# DAC_channel.net
KiCad netlist of a schematic drawn in Altium Designer
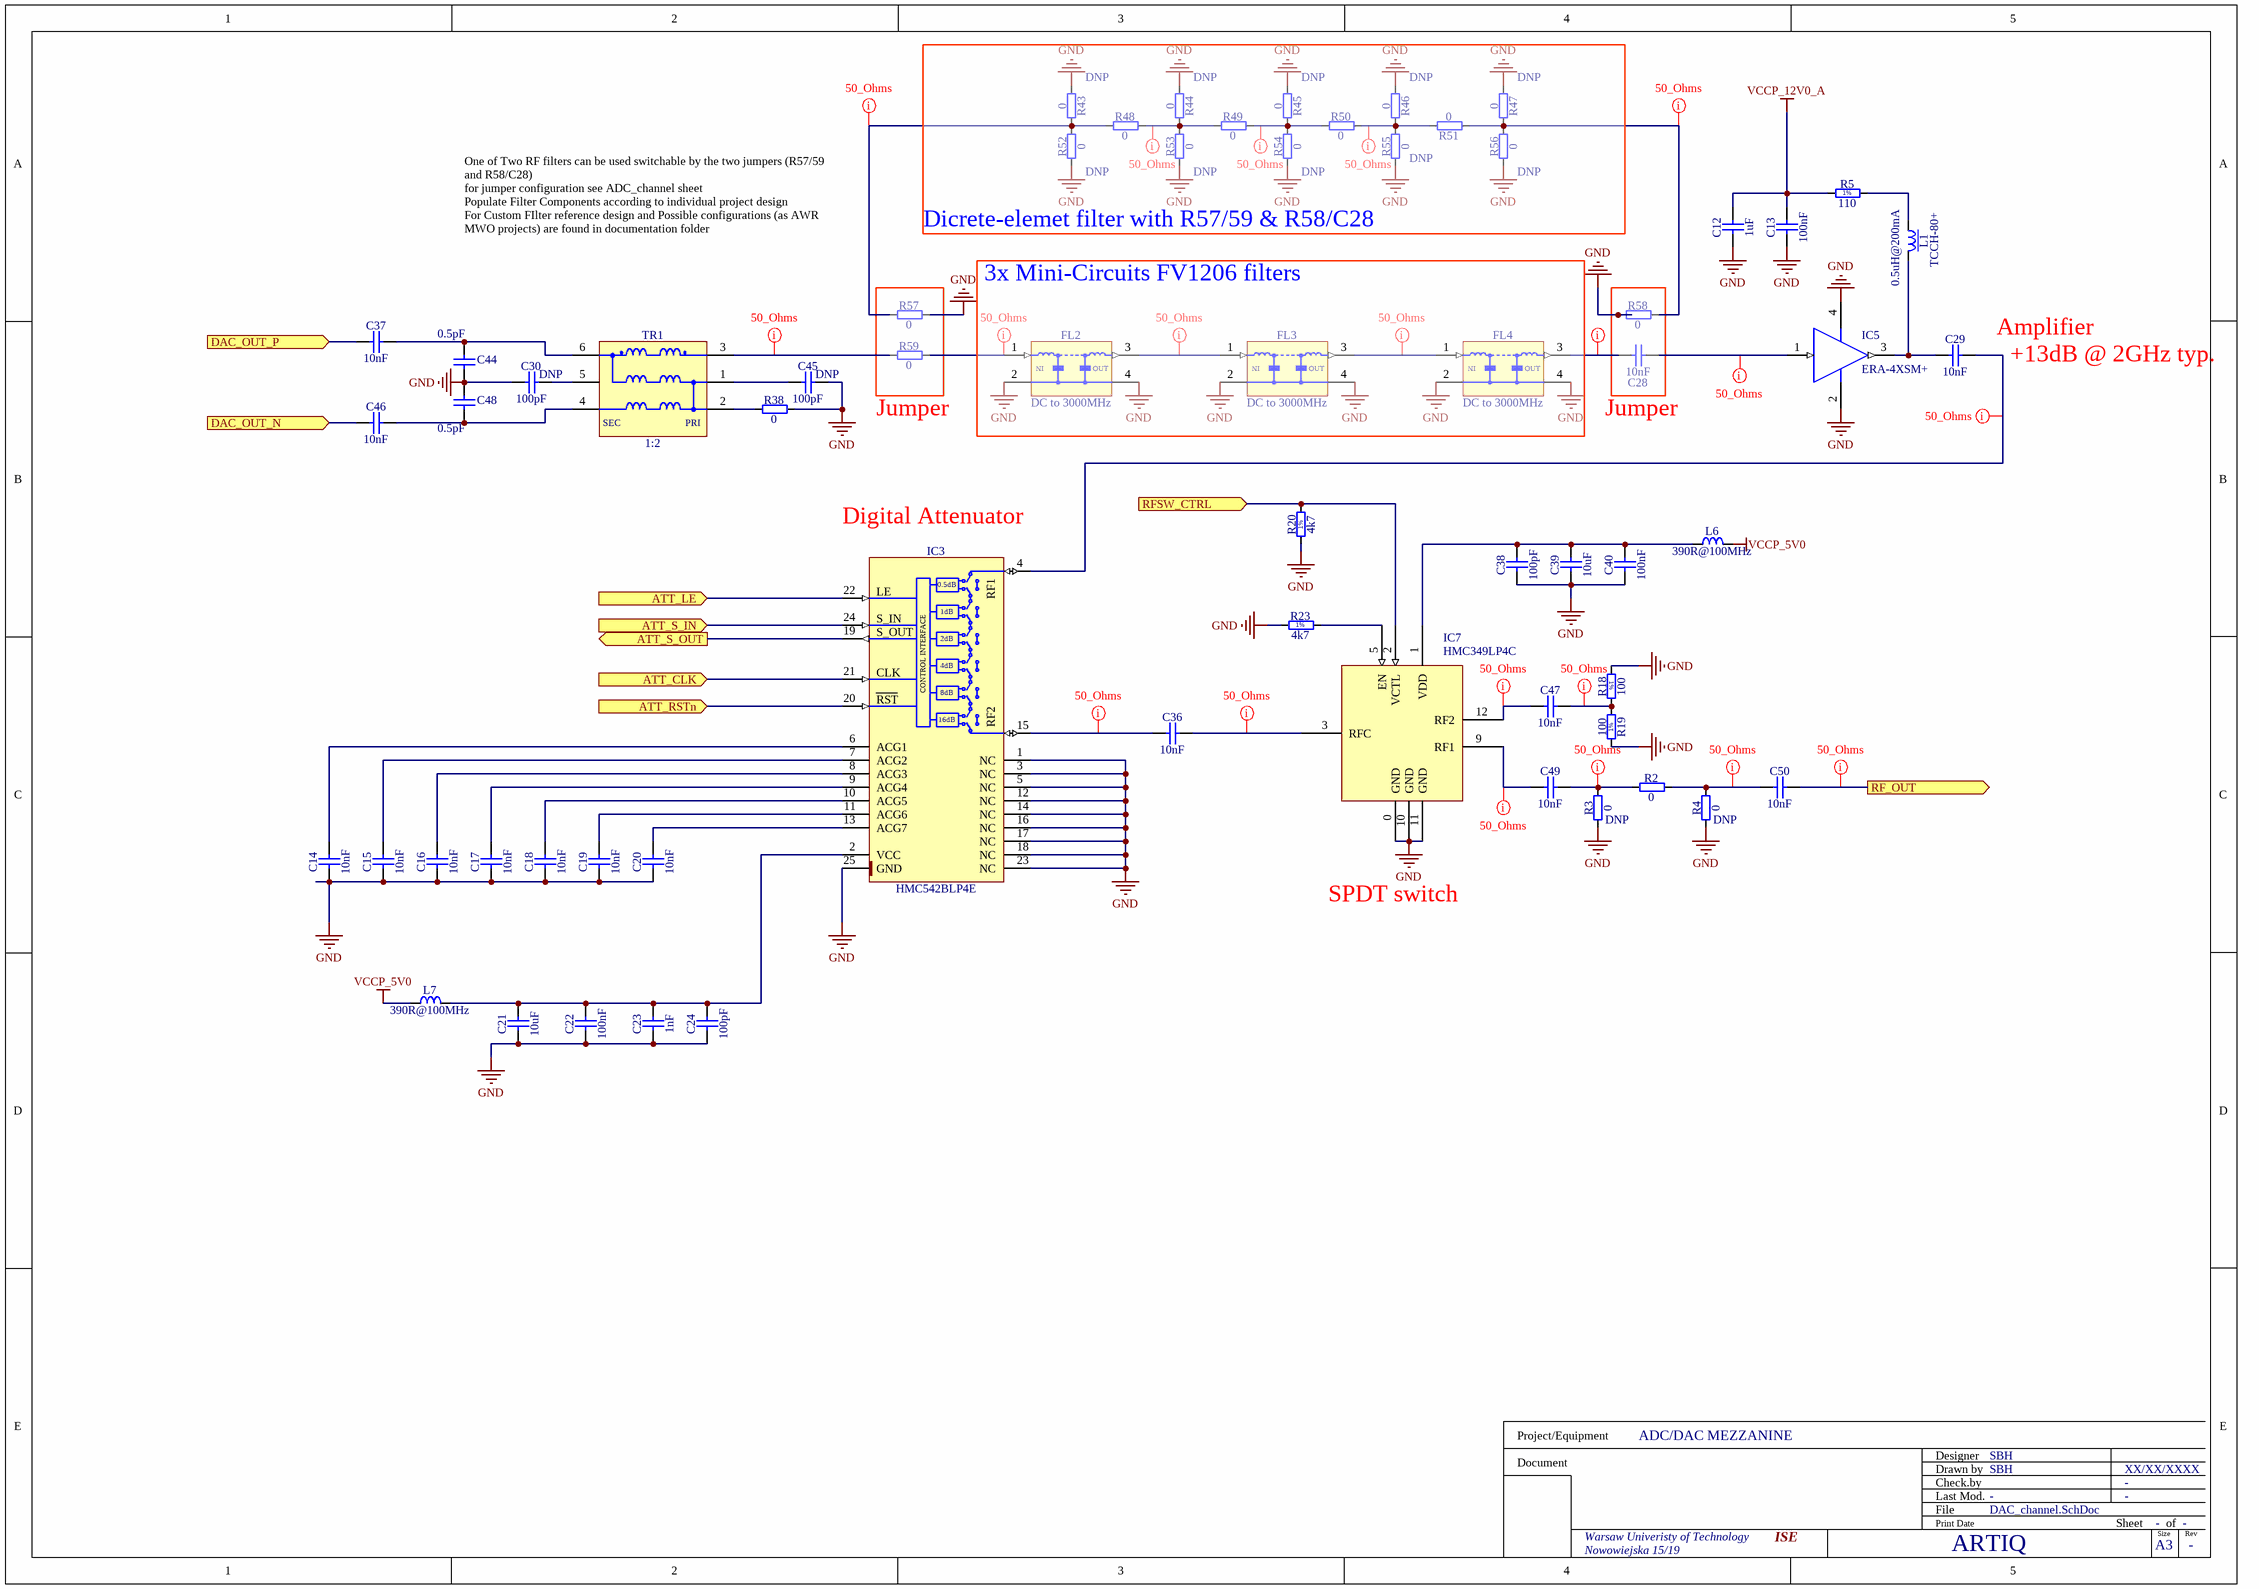
[diagram p0: DAC_channel.SchDoc]

(export (version "E")
  (design (tool "Eeschema 10.0.6"))
  (components
    (comp (ref "C12")
      (value "1uF")
      (footprint "CAPC2012X140N")
      (description "Non-polarised capacitor")
      (fields
        (field (name "PART NUMBER") "CC0805_1UF_35V_20%_X7R")
        (field (name "VOLTAGE") "35V")
        (field (name "AUTHOR") "CERN DEM JLC")
      )
      (libsource (lib "Capacitors") (part "Capacitor - non polarized"))
    )
    (comp (ref "C13")
      (value "100nF")
      (footprint "CAPC1608X87N")
      (description "Non-polarised capacitor")
      (fields
        (field (name "PART NUMBER") "CC0603_100NF_50V_10%_X7R")
        (field (name "VOLTAGE") "50V")
        (field (name "AUTHOR") "CERN DEM JLC")
      )
      (libsource (lib "Capacitors") (part "Capacitor - non polarized"))
    )
    (comp (ref "C14")
      (value "10nF")
      (footprint "CAPC1005X55N")
      (description "Non-polarised capacitor")
      (fields
        (field (name "PART NUMBER") "CC0402_10NF_16V_10%_X7R")
        (field (name "VOLTAGE") "16V")
        (field (name "AUTHOR") "CERN DEM JLC")
      )
      (libsource (lib "Capacitors") (part "Capacitor - non polarized"))
    )
    (comp (ref "C15")
      (value "10nF")
      (footprint "CAPC1005X55N")
      (description "Non-polarised capacitor")
      (fields
        (field (name "PART NUMBER") "CC0402_10NF_16V_10%_X7R")
        (field (name "VOLTAGE") "16V")
        (field (name "AUTHOR") "CERN DEM JLC")
      )
      (libsource (lib "Capacitors") (part "Capacitor - non polarized"))
    )
    (comp (ref "C16")
      (value "10nF")
      (footprint "CAPC1005X55N")
      (description "Non-polarised capacitor")
      (fields
        (field (name "PART NUMBER") "CC0402_10NF_16V_10%_X7R")
        (field (name "VOLTAGE") "16V")
        (field (name "AUTHOR") "CERN DEM JLC")
      )
      (libsource (lib "Capacitors") (part "Capacitor - non polarized"))
    )
    (comp (ref "C17")
      (value "10nF")
      (footprint "CAPC1005X55N")
      (description "Non-polarised capacitor")
      (fields
        (field (name "PART NUMBER") "CC0402_10NF_16V_10%_X7R")
        (field (name "VOLTAGE") "16V")
        (field (name "AUTHOR") "CERN DEM JLC")
      )
      (libsource (lib "Capacitors") (part "Capacitor - non polarized"))
    )
    (comp (ref "C18")
      (value "10nF")
      (footprint "CAPC1005X55N")
      (description "Non-polarised capacitor")
      (fields
        (field (name "PART NUMBER") "CC0402_10NF_16V_10%_X7R")
        (field (name "VOLTAGE") "16V")
        (field (name "AUTHOR") "CERN DEM JLC")
      )
      (libsource (lib "Capacitors") (part "Capacitor - non polarized"))
    )
    (comp (ref "C19")
      (value "10nF")
      (footprint "CAPC1005X55N")
      (description "Non-polarised capacitor")
      (fields
        (field (name "PART NUMBER") "CC0402_10NF_16V_10%_X7R")
        (field (name "VOLTAGE") "16V")
        (field (name "AUTHOR") "CERN DEM JLC")
      )
      (libsource (lib "Capacitors") (part "Capacitor - non polarized"))
    )
    (comp (ref "C20")
      (value "10nF")
      (footprint "CAPC1005X55N")
      (description "Non-polarised capacitor")
      (fields
        (field (name "PART NUMBER") "CC0402_10NF_16V_10%_X7R")
        (field (name "VOLTAGE") "16V")
        (field (name "AUTHOR") "CERN DEM JLC")
      )
      (libsource (lib "Capacitors") (part "Capacitor - non polarized"))
    )
    (comp (ref "C21")
      (value "10uF")
      (footprint "CAPC1608X80N")
      (description "Non-polarised capacitor")
      (fields
        (field (name "PART NUMBER") "CC0603_10UF_16V_20%_X5R")
        (field (name "VOLTAGE") "16V")
        (field (name "AUTHOR") "CERN DEM MR")
      )
      (libsource (lib "Capacitors") (part "Capacitor - non polarized"))
    )
    (comp (ref "C22")
      (value "100nF")
      (footprint "CAPC1005X55N")
      (description "Non-polarised capacitor")
      (fields
        (field (name "PART NUMBER") "CC0402_100NF_16V_10%_X7R")
        (field (name "VOLTAGE") "16V")
        (field (name "AUTHOR") "CERN DEM JLC")
      )
      (libsource (lib "Capacitors") (part "Capacitor - non polarized"))
    )
    (comp (ref "C23")
      (value "1nF")
      (footprint "CAPC1005X55N")
      (description "Non-polarised capacitor")
      (fields
        (field (name "PART NUMBER") "CC0402_1NF_50V_10%_X7R")
        (field (name "VOLTAGE") "50V")
        (field (name "AUTHOR") "CERN DEM JLC")
      )
      (libsource (lib "Capacitors") (part "Capacitor - non polarized"))
    )
    (comp (ref "C24")
      (value "100pF")
      (footprint "CAPC1005X55N")
      (description "Non-polarised capacitor")
      (fields
        (field (name "PART NUMBER") "CC0402_100PF_50V_5%_C0G")
        (field (name "VOLTAGE") "50V")
        (field (name "AUTHOR") "CERN DEM JLC")
      )
      (libsource (lib "Capacitors") (part "Capacitor - non polarized"))
    )
    (comp (ref "C28")
      (value "10nF")
      (footprint "CAPC1005X55N")
      (description "Non-polarised capacitor")
      (fields
        (field (name "PART NUMBER") "CC0402_10NF_16V_10%_X7R")
        (field (name "VOLTAGE") "16V")
        (field (name "AUTHOR") "CERN DEM JLC")
      )
      (libsource (lib "Capacitors") (part "Capacitor - non polarized"))
    )
    (comp (ref "C29")
      (value "10nF")
      (footprint "CAPC1005X55N")
      (description "Non-polarised capacitor")
      (fields
        (field (name "PART NUMBER") "CC0402_10NF_16V_10%_X7R")
        (field (name "VOLTAGE") "16V")
        (field (name "AUTHOR") "CERN DEM JLC")
      )
      (libsource (lib "Capacitors") (part "Capacitor - non polarized"))
    )
    (comp (ref "C30")
      (value "100pF")
      (footprint "CAPC1005X55N")
      (description "Non-polarised capacitor")
      (fields
        (field (name "PART NUMBER") "CC0402_100PF_50V_5%_C0G")
        (field (name "VOLTAGE") "50V")
        (field (name "MOUNTED") "DNP")
        (field (name "AUTHOR") "CERN DEM JLC")
      )
      (libsource (lib "Capacitors") (part "Capacitor - non polarized"))
    )
    (comp (ref "C36")
      (value "10nF")
      (footprint "CAPC1005X55N")
      (description "Non-polarised capacitor")
      (fields
        (field (name "PART NUMBER") "CC0402_10NF_16V_10%_X7R")
        (field (name "VOLTAGE") "16V")
        (field (name "AUTHOR") "CERN DEM JLC")
      )
      (libsource (lib "Capacitors") (part "Capacitor - non polarized"))
    )
    (comp (ref "C37")
      (value "10nF")
      (footprint "CAPC1005X55N")
      (description "Non-polarised capacitor")
      (fields
        (field (name "PART NUMBER") "CC0402_10NF_16V_10%_X7R")
        (field (name "VOLTAGE") "16V")
        (field (name "AUTHOR") "CERN DEM JLC")
      )
      (libsource (lib "Capacitors") (part "Capacitor - non polarized"))
    )
    (comp (ref "C38")
      (value "100pF")
      (footprint "CAPC1005X55N")
      (description "Non-polarised capacitor")
      (fields
        (field (name "PART NUMBER") "CC0402_100PF_50V_5%_C0G")
        (field (name "VOLTAGE") "50V")
        (field (name "AUTHOR") "CERN DEM JLC")
      )
      (libsource (lib "Capacitors") (part "Capacitor - non polarized"))
    )
    (comp (ref "C39")
      (value "10uF")
      (footprint "CAPC1608X80N")
      (description "Non-polarised capacitor")
      (fields
        (field (name "PART NUMBER") "CC0603_10UF_16V_20%_X5R")
        (field (name "VOLTAGE") "16V")
        (field (name "AUTHOR") "CERN DEM MR")
      )
      (libsource (lib "Capacitors") (part "Capacitor - non polarized"))
    )
    (comp (ref "C40")
      (value "100nF")
      (footprint "CAPC1005X55N")
      (description "Non-polarised capacitor")
      (fields
        (field (name "PART NUMBER") "CC0402_100NF_16V_10%_X7R")
        (field (name "VOLTAGE") "16V")
        (field (name "AUTHOR") "CERN DEM JLC")
      )
      (libsource (lib "Capacitors") (part "Capacitor - non polarized"))
    )
    (comp (ref "C44")
      (value "0.5pF")
      (footprint "CAPC0402(1005)60_M")
      (description "CAP 0.5pF 10V ±0.1pF 0402 (1005 Metric) Thickness 0.6mm SMD")
      (fields (field (name "TOLERANCE") "Â±0.1pF"))
      (libsource (lib "Altium Content Vault") (part "CMP-1034-00013-1"))
    )
    (comp (ref "C45")
      (value "100pF")
      (footprint "CAPC1005X55N")
      (description "Non-polarised capacitor")
      (fields
        (field (name "PART NUMBER") "CC0402_100PF_50V_5%_C0G")
        (field (name "VOLTAGE") "50V")
        (field (name "MOUNTED") "DNP")
        (field (name "AUTHOR") "CERN DEM JLC")
      )
      (libsource (lib "Capacitors") (part "Capacitor - non polarized"))
    )
    (comp (ref "C46")
      (value "10nF")
      (footprint "CAPC1005X55N")
      (description "Non-polarised capacitor")
      (fields
        (field (name "PART NUMBER") "CC0402_10NF_16V_10%_X7R")
        (field (name "VOLTAGE") "16V")
        (field (name "AUTHOR") "CERN DEM JLC")
      )
      (libsource (lib "Capacitors") (part "Capacitor - non polarized"))
    )
    (comp (ref "C47")
      (value "10nF")
      (footprint "CAPC1005X55N")
      (description "Non-polarised capacitor")
      (fields
        (field (name "PART NUMBER") "CC0402_10NF_16V_10%_X7R")
        (field (name "VOLTAGE") "16V")
        (field (name "AUTHOR") "CERN DEM JLC")
      )
      (libsource (lib "Capacitors") (part "Capacitor - non polarized"))
    )
    (comp (ref "C48")
      (value "0.5pF")
      (footprint "CAPC0402(1005)60_M")
      (description "CAP 0.5pF 10V ±0.1pF 0402 (1005 Metric) Thickness 0.6mm SMD")
      (fields (field (name "TOLERANCE") "Â±0.1pF"))
      (libsource (lib "Altium Content Vault") (part "CMP-1034-00013-1"))
    )
    (comp (ref "C49")
      (value "10nF")
      (footprint "CAPC1005X55N")
      (description "Non-polarised capacitor")
      (fields
        (field (name "PART NUMBER") "CC0402_10NF_16V_10%_X7R")
        (field (name "VOLTAGE") "16V")
        (field (name "AUTHOR") "CERN DEM JLC")
      )
      (libsource (lib "Capacitors") (part "Capacitor - non polarized"))
    )
    (comp (ref "C50")
      (value "10nF")
      (footprint "CAPC1005X55N")
      (description "Non-polarised capacitor")
      (fields
        (field (name "PART NUMBER") "CC0402_10NF_16V_10%_X7R")
        (field (name "VOLTAGE") "16V")
        (field (name "AUTHOR") "CERN DEM JLC")
      )
      (libsource (lib "Capacitors") (part "Capacitor - non polarized"))
    )
    (comp (ref "FL2")
      (value "DC to 3000MHz")
      (footprint "FIL_MINI-CIRCUITS_FV1206")
      (description "50 Ohm DC to 3000MHz Low Pass Filter")
      (fields
        (field (name "PART NUMBER") "FIL_MINI-CIRCUITS_LFCN-3000+")
        (field (name "MANUFACTURER") "MINI-CIRCUITS")
        (field (name "AUTHOR") "CERN DEM JLC")
      )
      (libsource (lib "Inductors & Transformers") (part "FIL_MINI-CIRCUITS_LFCN-3000+"))
    )
    (comp (ref "FL3")
      (value "DC to 3000MHz")
      (footprint "FIL_MINI-CIRCUITS_FV1206")
      (description "50 Ohm DC to 3000MHz Low Pass Filter")
      (fields
        (field (name "PART NUMBER") "FIL_MINI-CIRCUITS_LFCN-3000+")
        (field (name "MANUFACTURER") "MINI-CIRCUITS")
        (field (name "AUTHOR") "CERN DEM JLC")
      )
      (libsource (lib "Inductors & Transformers") (part "FIL_MINI-CIRCUITS_LFCN-3000+"))
    )
    (comp (ref "FL4")
      (value "DC to 3000MHz")
      (footprint "FIL_MINI-CIRCUITS_FV1206")
      (description "50 Ohm DC to 3000MHz Low Pass Filter")
      (fields
        (field (name "PART NUMBER") "FIL_MINI-CIRCUITS_LFCN-3000+")
        (field (name "MANUFACTURER") "MINI-CIRCUITS")
        (field (name "AUTHOR") "CERN DEM JLC")
      )
      (libsource (lib "Inductors & Transformers") (part "FIL_MINI-CIRCUITS_LFCN-3000+"))
    )
    (comp (ref "IC3")
      (value "HMC542BLP4E")
      (footprint "QFN50P400X400X100-25N-S295")
      (description "0.5dB LSB GaAs MMIC 6-bit Digital Serial Control Attenuator, DC - 4GHz")
      (fields (field (name "MANUFACTURER") "HITTITE MICROWAVE CORP") (field (name "AUTHOR") "CERN DEM JMW"))
      (libsource (lib "ICs And Semiconductors") (part "HMC542BLP4E"))
    )
    (comp (ref "IC5")
      (value "ERA-4XSM+")
      (footprint "MINI-CIRCUITS_WW107")
      (description "DC-4GHz Monolithic Amplifier")
      (fields (field (name "MANUFACTURER") "MINI-CIRCUITS") (field (name "AUTHOR") "CERN DEM JMW"))
      (libsource (lib "ICs And Semiconductors") (part "ERA-4XSM+"))
    )
    (comp (ref "IC7")
      (value "HMC349LP4C")
      (footprint "uRFB_CLKIN3:QFN65P400X400X100-16N")
      (description "Hittite RF Switch, SPDT, Non-Reflective")
      (libsource (lib "uRFB_CLKIN3") (part "HMC349LP4C"))
    )
    (comp (ref "L1")
      (value "0.5uH@200mA")
      (footprint "IND_MINI-CIRCUITS_GU1604")
      (description "50 Ohms, 50 to 8200 MHz RF Choke")
      (fields
        (field (name "PART NUMBER") "IND_MINI-CIRCUITS_TCCH-80+")
        (field (name "POWER") "200mA")
        (field (name "MANUFACTURER PART NUMBER") "TCCH-80+")
        (field (name "AUTHOR") "CERN DEM JLC")
      )
      (libsource (lib "Inductors & Transformers") (part "IND_MINI-CIRCUITS_TCCH-80+"))
    )
    (comp (ref "L6")
      (value "390R@100MHz")
      (footprint "INDC1608X95N")
      (description "Inductor")
      (fields
        (field (name "PART NUMBER") "IND0603_TDK_MPZ1608R391A")
        (field (name "POWER") "1.2A")
        (field (name "AUTHOR") "CERN DEM JLC")
      )
      (libsource (lib "Inductors & Transformers") (part "Inductor"))
    )
    (comp (ref "L7")
      (value "390R@100MHz")
      (footprint "INDC1608X95N")
      (description "Inductor")
      (fields
        (field (name "PART NUMBER") "IND0603_TDK_MPZ1608R391A")
        (field (name "POWER") "1.2A")
        (field (name "AUTHOR") "CERN DEM JLC")
      )
      (libsource (lib "Inductors & Transformers") (part "Inductor"))
    )
    (comp (ref "R2")
      (value "0")
      (footprint "RESC1005X40N")
      (description "Resistor")
      (fields
        (field (name "PART NUMBER") "R0402_0R_JUMPER")
        (field (name "MANUFACTURER") "GENERIC")
        (field (name "AUTHOR") "CERN DEM JLC")
      )
      (libsource (lib "Resistors") (part "Resistor"))
    )
    (comp (ref "R3")
      (value "0")
      (footprint "RESC1005X40N")
      (description "Resistor")
      (fields
        (field (name "PART NUMBER") "R0402_0R_JUMPER")
        (field (name "MANUFACTURER") "GENERIC")
        (field (name "MOUNTED") "DNP")
        (field (name "AUTHOR") "CERN DEM JLC")
      )
      (libsource (lib "Resistors") (part "Resistor"))
    )
    (comp (ref "R4")
      (value "0")
      (footprint "RESC1005X40N")
      (description "Resistor")
      (fields
        (field (name "PART NUMBER") "R0402_0R_JUMPER")
        (field (name "MANUFACTURER") "GENERIC")
        (field (name "MOUNTED") "DNP")
        (field (name "AUTHOR") "CERN DEM JLC")
      )
      (libsource (lib "Resistors") (part "Resistor"))
    )
    (comp (ref "R5")
      (value "110")
      (footprint "RESC1005X40N")
      (description "Resistor - 1%")
      (fields
        (field (name "PART NUMBER") "R0402_110R_1%_0.0625W_100PPM")
        (field (name "POWER") "0.0625W")
        (field (name "AUTHOR") "CERN DEM JLC")
      )
      (libsource (lib "Resistors") (part "Resistor - 1%"))
    )
    (comp (ref "R18")
      (value "100")
      (footprint "RESC0603X28N")
      (description "Resistor - 1%")
      (fields
        (field (name "PART NUMBER") "R0201_100R_1%_0.05W_200PPM")
        (field (name "POWER") "0.05W")
        (field (name "AUTHOR") "CERN DEM JLC")
      )
      (libsource (lib "Resistors") (part "Resistor - 1%"))
    )
    (comp (ref "R19")
      (value "100")
      (footprint "RESC0603X28N")
      (description "Resistor - 1%")
      (fields
        (field (name "PART NUMBER") "R0201_100R_1%_0.05W_200PPM")
        (field (name "POWER") "0.05W")
        (field (name "AUTHOR") "CERN DEM JLC")
      )
      (libsource (lib "Resistors") (part "Resistor - 1%"))
    )
    (comp (ref "R20")
      (value "4k7")
      (footprint "RESC1005X40N")
      (description "Resistor - 1%")
      (fields
        (field (name "PART NUMBER") "R0402_4K7_1%_0.0625W_100PPM")
        (field (name "POWER") "0.0625W")
        (field (name "AUTHOR") "CERN DEM JLC")
      )
      (libsource (lib "Resistors") (part "Resistor - 1%"))
    )
    (comp (ref "R23")
      (value "4k7")
      (footprint "RESC1005X40N")
      (description "Resistor - 1%")
      (fields
        (field (name "PART NUMBER") "R0402_4K7_1%_0.0625W_100PPM")
        (field (name "POWER") "0.0625W")
        (field (name "AUTHOR") "CERN DEM JLC")
      )
      (libsource (lib "Resistors") (part "Resistor - 1%"))
    )
    (comp (ref "R38")
      (value "0")
      (footprint "RESC1005X40N")
      (description "Resistor")
      (fields
        (field (name "PART NUMBER") "R0402_0R_JUMPER")
        (field (name "MANUFACTURER") "GENERIC")
        (field (name "AUTHOR") "CERN DEM JLC")
      )
      (libsource (lib "Resistors") (part "Resistor"))
    )
    (comp (ref "R43")
      (value "0")
      (footprint "RESC1005X40N")
      (description "Resistor")
      (fields
        (field (name "PART NUMBER") "R0402_0R_JUMPER")
        (field (name "MANUFACTURER") "GENERIC")
        (field (name "MOUNTED") "DNP")
        (field (name "AUTHOR") "CERN DEM JLC")
      )
      (libsource (lib "Resistors") (part "Resistor"))
    )
    (comp (ref "R44")
      (value "0")
      (footprint "RESC1005X40N")
      (description "Resistor")
      (fields
        (field (name "PART NUMBER") "R0402_0R_JUMPER")
        (field (name "MANUFACTURER") "GENERIC")
        (field (name "MOUNTED") "DNP")
        (field (name "AUTHOR") "CERN DEM JLC")
      )
      (libsource (lib "Resistors") (part "Resistor"))
    )
    (comp (ref "R45")
      (value "0")
      (footprint "RESC1005X40N")
      (description "Resistor")
      (fields
        (field (name "PART NUMBER") "R0402_0R_JUMPER")
        (field (name "MANUFACTURER") "GENERIC")
        (field (name "MOUNTED") "DNP")
        (field (name "AUTHOR") "CERN DEM JLC")
      )
      (libsource (lib "Resistors") (part "Resistor"))
    )
    (comp (ref "R46")
      (value "0")
      (footprint "RESC1005X40N")
      (description "Resistor")
      (fields
        (field (name "PART NUMBER") "R0402_0R_JUMPER")
        (field (name "MANUFACTURER") "GENERIC")
        (field (name "MOUNTED") "DNP")
        (field (name "AUTHOR") "CERN DEM JLC")
      )
      (libsource (lib "Resistors") (part "Resistor"))
    )
    (comp (ref "R47")
      (value "0")
      (footprint "RESC1005X40N")
      (description "Resistor")
      (fields
        (field (name "PART NUMBER") "R0402_0R_JUMPER")
        (field (name "MANUFACTURER") "GENERIC")
        (field (name "MOUNTED") "DNP")
        (field (name "AUTHOR") "CERN DEM JLC")
      )
      (libsource (lib "Resistors") (part "Resistor"))
    )
    (comp (ref "R48")
      (value "0")
      (footprint "RESC1005X40N")
      (description "Resistor")
      (fields
        (field (name "PART NUMBER") "R0402_0R_JUMPER")
        (field (name "MANUFACTURER") "GENERIC")
        (field (name "AUTHOR") "CERN DEM JLC")
      )
      (libsource (lib "Resistors") (part "Resistor"))
    )
    (comp (ref "R49")
      (value "0")
      (footprint "RESC1005X40N")
      (description "Resistor")
      (fields
        (field (name "PART NUMBER") "R0402_0R_JUMPER")
        (field (name "MANUFACTURER") "GENERIC")
        (field (name "AUTHOR") "CERN DEM JLC")
      )
      (libsource (lib "Resistors") (part "Resistor"))
    )
    (comp (ref "R50")
      (value "0")
      (footprint "RESC1005X40N")
      (description "Resistor")
      (fields
        (field (name "PART NUMBER") "R0402_0R_JUMPER")
        (field (name "MANUFACTURER") "GENERIC")
        (field (name "AUTHOR") "CERN DEM JLC")
      )
      (libsource (lib "Resistors") (part "Resistor"))
    )
    (comp (ref "R51")
      (value "0")
      (footprint "RESC1005X40N")
      (description "Resistor")
      (fields
        (field (name "PART NUMBER") "R0402_0R_JUMPER")
        (field (name "MANUFACTURER") "GENERIC")
        (field (name "AUTHOR") "CERN DEM JLC")
      )
      (libsource (lib "Resistors") (part "Resistor"))
    )
    (comp (ref "R52")
      (value "0")
      (footprint "RESC1005X40N")
      (description "Resistor")
      (fields
        (field (name "PART NUMBER") "R0402_0R_JUMPER")
        (field (name "MANUFACTURER") "GENERIC")
        (field (name "MOUNTED") "DNP")
        (field (name "AUTHOR") "CERN DEM JLC")
      )
      (libsource (lib "Resistors") (part "Resistor"))
    )
    (comp (ref "R53")
      (value "0")
      (footprint "RESC1005X40N")
      (description "Resistor")
      (fields
        (field (name "PART NUMBER") "R0402_0R_JUMPER")
        (field (name "MANUFACTURER") "GENERIC")
        (field (name "MOUNTED") "DNP")
        (field (name "AUTHOR") "CERN DEM JLC")
      )
      (libsource (lib "Resistors") (part "Resistor"))
    )
    (comp (ref "R54")
      (value "0")
      (footprint "RESC1005X40N")
      (description "Resistor")
      (fields
        (field (name "PART NUMBER") "R0402_0R_JUMPER")
        (field (name "MANUFACTURER") "GENERIC")
        (field (name "MOUNTED") "DNP")
        (field (name "AUTHOR") "CERN DEM JLC")
      )
      (libsource (lib "Resistors") (part "Resistor"))
    )
    (comp (ref "R55")
      (value "0")
      (footprint "RESC1005X40N")
      (description "Resistor")
      (fields
        (field (name "PART NUMBER") "R0402_0R_JUMPER")
        (field (name "MANUFACTURER") "GENERIC")
        (field (name "MOUNTED") "DNP")
        (field (name "AUTHOR") "CERN DEM JLC")
      )
      (libsource (lib "Resistors") (part "Resistor"))
    )
    (comp (ref "R56")
      (value "0")
      (footprint "RESC1005X40N")
      (description "Resistor")
      (fields
        (field (name "PART NUMBER") "R0402_0R_JUMPER")
        (field (name "MANUFACTURER") "GENERIC")
        (field (name "MOUNTED") "DNP")
        (field (name "AUTHOR") "CERN DEM JLC")
      )
      (libsource (lib "Resistors") (part "Resistor"))
    )
    (comp (ref "R57")
      (value "0")
      (footprint "RESC1005X40N")
      (description "Resistor")
      (fields
        (field (name "PART NUMBER") "R0402_0R_JUMPER")
        (field (name "MANUFACTURER") "GENERIC")
        (field (name "AUTHOR") "CERN DEM JLC")
      )
      (libsource (lib "Resistors") (part "Resistor"))
    )
    (comp (ref "R58")
      (value "0")
      (footprint "RESC1005X40N")
      (description "Resistor")
      (fields
        (field (name "PART NUMBER") "R0402_0R_JUMPER")
        (field (name "MANUFACTURER") "GENERIC")
        (field (name "AUTHOR") "CERN DEM JLC")
      )
      (libsource (lib "Resistors") (part "Resistor"))
    )
    (comp (ref "R59")
      (value "0")
      (footprint "RESC1005X40N")
      (description "Resistor")
      (fields
        (field (name "PART NUMBER") "R0402_0R_JUMPER")
        (field (name "MANUFACTURER") "GENERIC")
        (field (name "AUTHOR") "CERN DEM JLC")
      )
      (libsource (lib "Resistors") (part "Resistor"))
    )
    (comp (ref "TR1")
      (value "1:2")
      (footprint "XFMR_MINI-CIRCUITS_DB1627")
      (description "50 OHMS 10 to 4000 MHz RF Transformer")
      (fields
        (field (name "PART NUMBER") "XFMR_MINI-CIRCUITS_TCM2-43X+")
        (field (name "POWER") "0.4W")
        (field (name "AUTHOR") "CERN DEM BC")
      )
      (libsource (lib "Inductors & Transformers") (part "XFMR_MINI-CIRCUITS_TCM2-43X"))
    )
  )
  (nets
    (net (code "1") (name "/ATT_CLK") (class "Default")
      (node (ref "IC3") (pin "21") (pinfunction "SHIFT_CLOCK_21") (pintype "input"))
    )
    (net (code "2") (name "/ATT_LE") (class "Default")
      (node (ref "IC3") (pin "22") (pinfunction "LATCH_ENABLE_22") (pintype "input"))
    )
    (net (code "3") (name "/ATT_RSTn") (class "Default")
      (node (ref "IC3") (pin "20") (pinfunction "~{RESET}_20") (pintype "input"))
    )
    (net (code "4") (name "/ATT_S_IN") (class "Default")
      (node (ref "IC3") (pin "24") (pinfunction "SERIAL_INPUT_24") (pintype "input"))
    )
    (net (code "5") (name "/ATT_S_OUT") (class "Default")
      (node (ref "IC3") (pin "19") (pinfunction "SERIAL_OUTPUT_19") (pintype "output"))
    )
    (net (code "6") (name "/DAC_OUT_N") (class "Default")
      (node (ref "C46") (pin "1") (pinfunction "1_1") (pintype "passive"))
    )
    (net (code "7") (name "/DAC_OUT_P") (class "Default")
      (node (ref "C37") (pin "1") (pinfunction "1_1") (pintype "passive"))
    )
    (net (code "8") (name "/RFSW_CTRL") (class "Default")
      (node (ref "IC7") (pin "2") (pinfunction "VCTL_2") (pintype "input"))
      (node (ref "R20") (pin "2") (pinfunction "2_2") (pintype "passive"))
    )
    (net (code "9") (name "/RF_OUT") (class "Default")
      (node (ref "C50") (pin "2") (pinfunction "2_2") (pintype "passive"))
    )
    (net (code "10") (name "GND") (class "Default")
      (node (ref "C12") (pin "1") (pinfunction "1_1") (pintype "passive"))
      (node (ref "C13") (pin "1") (pinfunction "1_1") (pintype "passive"))
      (node (ref "C14") (pin "1") (pinfunction "1_1") (pintype "passive"))
      (node (ref "C15") (pin "1") (pinfunction "1_1") (pintype "passive"))
      (node (ref "C16") (pin "1") (pinfunction "1_1") (pintype "passive"))
      (node (ref "C17") (pin "1") (pinfunction "1_1") (pintype "passive"))
      (node (ref "C18") (pin "1") (pinfunction "1_1") (pintype "passive"))
      (node (ref "C19") (pin "1") (pinfunction "1_1") (pintype "passive"))
      (node (ref "C20") (pin "1") (pinfunction "1_1") (pintype "passive"))
      (node (ref "C21") (pin "1") (pinfunction "1_1") (pintype "passive"))
      (node (ref "C22") (pin "1") (pinfunction "1_1") (pintype "passive"))
      (node (ref "C23") (pin "1") (pinfunction "1_1") (pintype "passive"))
      (node (ref "C24") (pin "1") (pinfunction "1_1") (pintype "passive"))
      (node (ref "C30") (pin "1") (pinfunction "1_1") (pintype "passive"))
      (node (ref "C38") (pin "2") (pinfunction "2_2") (pintype "passive"))
      (node (ref "C39") (pin "1") (pinfunction "1_1") (pintype "passive"))
      (node (ref "C40") (pin "1") (pinfunction "1_1") (pintype "passive"))
      (node (ref "C44") (pin "1") (pinfunction "1_1") (pintype "passive"))
      (node (ref "C45") (pin "2") (pinfunction "2_2") (pintype "passive"))
      (node (ref "C48") (pin "2") (pinfunction "2_2") (pintype "passive"))
      (node (ref "FL2") (pin "2") (pinfunction "GND_2") (pintype "power_in"))
      (node (ref "FL2") (pin "4") (pinfunction "GND_4") (pintype "power_in"))
      (node (ref "FL3") (pin "2") (pinfunction "GND_2") (pintype "power_in"))
      (node (ref "FL3") (pin "4") (pinfunction "GND_4") (pintype "power_in"))
      (node (ref "FL4") (pin "2") (pinfunction "GND_2") (pintype "power_in"))
      (node (ref "FL4") (pin "4") (pinfunction "GND_4") (pintype "power_in"))
      (node (ref "IC3") (pin "1") (pinfunction "NC_1") (pintype "passive"))
      (node (ref "IC3") (pin "12") (pinfunction "NC_12") (pintype "passive"))
      (node (ref "IC3") (pin "14") (pinfunction "NC_14") (pintype "passive"))
      (node (ref "IC3") (pin "16") (pinfunction "NC_16") (pintype "passive"))
      (node (ref "IC3") (pin "17") (pinfunction "NC_17") (pintype "passive"))
      (node (ref "IC3") (pin "18") (pinfunction "NC_18") (pintype "passive"))
      (node (ref "IC3") (pin "23") (pinfunction "NC_23") (pintype "passive"))
      (node (ref "IC3") (pin "25") (pinfunction "GND_25") (pintype "power_in"))
      (node (ref "IC3") (pin "3") (pinfunction "NC_3") (pintype "passive"))
      (node (ref "IC3") (pin "5") (pinfunction "NC_5") (pintype "passive"))
      (node (ref "IC5") (pin "2") (pinfunction "GND_2") (pintype "power_in"))
      (node (ref "IC5") (pin "4") (pinfunction "GND_4") (pintype "power_in"))
      (node (ref "IC7") (pin "0") (pinfunction "GND_0") (pintype "power_in"))
      (node (ref "IC7") (pin "10") (pinfunction "GND_10") (pintype "power_in"))
      (node (ref "IC7") (pin "11") (pinfunction "GND_11") (pintype "power_in"))
      (node (ref "R18") (pin "1") (pinfunction "1_1") (pintype "passive"))
      (node (ref "R19") (pin "1") (pinfunction "1_1") (pintype "passive"))
      (node (ref "R20") (pin "1") (pinfunction "1_1") (pintype "passive"))
      (node (ref "R23") (pin "1") (pinfunction "1_1") (pintype "passive"))
      (node (ref "R3") (pin "1") (pinfunction "1_1") (pintype "passive"))
      (node (ref "R38") (pin "2") (pinfunction "2_2") (pintype "passive"))
      (node (ref "R4") (pin "1") (pinfunction "1_1") (pintype "passive"))
      (node (ref "R43") (pin "1") (pinfunction "1_1") (pintype "passive"))
      (node (ref "R44") (pin "1") (pinfunction "1_1") (pintype "passive"))
      (node (ref "R45") (pin "1") (pinfunction "1_1") (pintype "passive"))
      (node (ref "R46") (pin "1") (pinfunction "1_1") (pintype "passive"))
      (node (ref "R47") (pin "1") (pinfunction "1_1") (pintype "passive"))
      (node (ref "R52") (pin "1") (pinfunction "1_1") (pintype "passive"))
      (node (ref "R53") (pin "1") (pinfunction "1_1") (pintype "passive"))
      (node (ref "R54") (pin "1") (pinfunction "1_1") (pintype "passive"))
      (node (ref "R55") (pin "1") (pinfunction "1_1") (pintype "passive"))
      (node (ref "R56") (pin "1") (pinfunction "1_1") (pintype "passive"))
      (node (ref "R57") (pin "2") (pinfunction "2_2") (pintype "passive"))
      (node (ref "R58") (pin "2") (pinfunction "2_2") (pintype "passive"))
    )
    (net (code "11") (name "Net-(C37-Pad2)") (class "Default")
      (node (ref "C37") (pin "2") (pinfunction "2_2") (pintype "passive"))
      (node (ref "C44") (pin "2") (pinfunction "2_2") (pintype "passive"))
      (node (ref "TR1") (pin "6") (pinfunction "S1_6") (pintype "passive"))
    )
    (net (code "12") (name "Net-(C45-Pad1)") (class "Default")
      (node (ref "C45") (pin "1") (pinfunction "1_1") (pintype "passive"))
      (node (ref "TR1") (pin "1") (pinfunction "P1_1") (pintype "passive"))
    )
    (net (code "13") (name "Net-(C46-Pad2)") (class "Default")
      (node (ref "C46") (pin "2") (pinfunction "2_2") (pintype "passive"))
      (node (ref "C48") (pin "1") (pinfunction "1_1") (pintype "passive"))
      (node (ref "TR1") (pin "4") (pinfunction "S1_4") (pintype "passive"))
    )
    (net (code "14") (name "Net-(C47-Pad2)") (class "Default")
      (node (ref "C47") (pin "2") (pinfunction "2_2") (pintype "passive"))
      (node (ref "R18") (pin "2") (pinfunction "2_2") (pintype "passive"))
      (node (ref "R19") (pin "2") (pinfunction "2_2") (pintype "passive"))
    )
    (net (code "15") (name "Net-(C49-Pad2)") (class "Default")
      (node (ref "C49") (pin "2") (pinfunction "2_2") (pintype "passive"))
      (node (ref "R2") (pin "1") (pinfunction "1_1") (pintype "passive"))
      (node (ref "R3") (pin "2") (pinfunction "2_2") (pintype "passive"))
    )
    (net (code "16") (name "Net-(C50-Pad1)") (class "Default")
      (node (ref "C50") (pin "1") (pinfunction "1_1") (pintype "passive"))
      (node (ref "R2") (pin "2") (pinfunction "2_2") (pintype "passive"))
      (node (ref "R4") (pin "2") (pinfunction "2_2") (pintype "passive"))
    )
    (net (code "17") (name "Net-(FL2-RFIN)") (class "Default")
      (node (ref "FL2") (pin "1") (pinfunction "RFIN_1") (pintype "input"))
      (node (ref "R59") (pin "2") (pinfunction "2_2") (pintype "passive"))
    )
    (net (code "18") (name "Net-(FL2-RFOUT)") (class "Default")
      (node (ref "FL2") (pin "3") (pinfunction "RFOUT_3") (pintype "output"))
      (node (ref "FL3") (pin "1") (pinfunction "RFIN_1") (pintype "input"))
    )
    (net (code "19") (name "Net-(FL3-RFOUT)") (class "Default")
      (node (ref "FL3") (pin "3") (pinfunction "RFOUT_3") (pintype "output"))
      (node (ref "FL4") (pin "1") (pinfunction "RFIN_1") (pintype "input"))
    )
    (net (code "20") (name "Net-(FL4-RFOUT)") (class "Default")
      (node (ref "C28") (pin "1") (pinfunction "1_1") (pintype "passive"))
      (node (ref "FL4") (pin "3") (pinfunction "RFOUT_3") (pintype "output"))
    )
    (net (code "21") (name "Net-(IC3-ACG1)") (class "Default")
      (node (ref "C14") (pin "2") (pinfunction "2_2") (pintype "passive"))
      (node (ref "IC3") (pin "6") (pinfunction "ACG1_6") (pintype "passive"))
    )
    (net (code "22") (name "Net-(IC3-ACG2)") (class "Default")
      (node (ref "C15") (pin "2") (pinfunction "2_2") (pintype "passive"))
      (node (ref "IC3") (pin "7") (pinfunction "ACG2_7") (pintype "passive"))
    )
    (net (code "23") (name "Net-(IC3-ACG3)") (class "Default")
      (node (ref "C16") (pin "2") (pinfunction "2_2") (pintype "passive"))
      (node (ref "IC3") (pin "8") (pinfunction "ACG3_8") (pintype "passive"))
    )
    (net (code "24") (name "Net-(IC3-ACG4)") (class "Default")
      (node (ref "C17") (pin "2") (pinfunction "2_2") (pintype "passive"))
      (node (ref "IC3") (pin "9") (pinfunction "ACG4_9") (pintype "passive"))
    )
    (net (code "25") (name "Net-(IC3-ACG5)") (class "Default")
      (node (ref "C18") (pin "2") (pinfunction "2_2") (pintype "passive"))
      (node (ref "IC3") (pin "10") (pinfunction "ACG5_10") (pintype "passive"))
    )
    (net (code "26") (name "Net-(IC3-ACG6)") (class "Default")
      (node (ref "C19") (pin "2") (pinfunction "2_2") (pintype "passive"))
      (node (ref "IC3") (pin "11") (pinfunction "ACG6_11") (pintype "passive"))
    )
    (net (code "27") (name "Net-(IC3-ACG7)") (class "Default")
      (node (ref "C20") (pin "2") (pinfunction "2_2") (pintype "passive"))
      (node (ref "IC3") (pin "13") (pinfunction "ACG7_13") (pintype "passive"))
    )
    (net (code "28") (name "Net-(IC3-RF1)") (class "Default")
      (node (ref "C29") (pin "2") (pinfunction "2_2") (pintype "passive"))
      (node (ref "IC3") (pin "4") (pinfunction "RF1_4") (pintype "bidirectional"))
    )
    (net (code "29") (name "Net-(IC3-RF2)") (class "Default")
      (node (ref "C36") (pin "1") (pinfunction "1_1") (pintype "passive"))
      (node (ref "IC3") (pin "15") (pinfunction "RF2_15") (pintype "bidirectional"))
    )
    (net (code "30") (name "Net-(IC3-VCC)") (class "Default")
      (node (ref "C21") (pin "2") (pinfunction "2_2") (pintype "passive"))
      (node (ref "C22") (pin "2") (pinfunction "2_2") (pintype "passive"))
      (node (ref "C23") (pin "2") (pinfunction "2_2") (pintype "passive"))
      (node (ref "C24") (pin "2") (pinfunction "2_2") (pintype "passive"))
      (node (ref "IC3") (pin "2") (pinfunction "VCC_2") (pintype "power_in"))
      (node (ref "L7") (pin "2") (pinfunction "2_2") (pintype "passive"))
    )
    (net (code "31") (name "Net-(IC5-RF_IN)") (class "Default")
      (node (ref "C28") (pin "2") (pinfunction "2_2") (pintype "passive"))
      (node (ref "IC5") (pin "1") (pinfunction "RF_IN_1") (pintype "input"))
    )
    (net (code "32") (name "Net-(IC5-RF_OUT)") (class "Default")
      (node (ref "C29") (pin "1") (pinfunction "1_1") (pintype "passive"))
      (node (ref "IC5") (pin "3") (pinfunction "RF_OUT_3") (pintype "output"))
      (node (ref "L1") (pin "3") (pinfunction "3_3") (pintype "passive"))
    )
    (net (code "33") (name "Net-(IC7-EN)") (class "Default")
      (node (ref "IC7") (pin "5") (pinfunction "EN_5") (pintype "input"))
      (node (ref "R23") (pin "2") (pinfunction "2_2") (pintype "passive"))
    )
    (net (code "34") (name "Net-(IC7-RF1)") (class "Default")
      (node (ref "C49") (pin "1") (pinfunction "1_1") (pintype "passive"))
      (node (ref "IC7") (pin "9") (pinfunction "RF1_9") (pintype "passive"))
    )
    (net (code "35") (name "Net-(IC7-RF2)") (class "Default")
      (node (ref "C47") (pin "1") (pinfunction "1_1") (pintype "passive"))
      (node (ref "IC7") (pin "12") (pinfunction "RF2_12") (pintype "passive"))
    )
    (net (code "36") (name "Net-(IC7-RFC)") (class "Default")
      (node (ref "C36") (pin "2") (pinfunction "2_2") (pintype "passive"))
      (node (ref "IC7") (pin "3") (pinfunction "RFC_3") (pintype "passive"))
    )
    (net (code "37") (name "Net-(IC7-VDD)") (class "Default")
      (node (ref "C38") (pin "1") (pinfunction "1_1") (pintype "passive"))
      (node (ref "C39") (pin "2") (pinfunction "2_2") (pintype "passive"))
      (node (ref "C40") (pin "2") (pinfunction "2_2") (pintype "passive"))
      (node (ref "IC7") (pin "1") (pinfunction "VDD_1") (pintype "power_in"))
      (node (ref "L6") (pin "1") (pinfunction "1_1") (pintype "passive"))
    )
    (net (code "38") (name "Net-(L1-Pad1)") (class "Default")
      (node (ref "L1") (pin "1") (pinfunction "1_1") (pintype "passive"))
      (node (ref "R5") (pin "2") (pinfunction "2_2") (pintype "passive"))
    )
    (net (code "39") (name "Net-(R38-Pad1)") (class "Default")
      (node (ref "R38") (pin "1") (pinfunction "1_1") (pintype "passive"))
      (node (ref "TR1") (pin "2") (pinfunction "P1_2") (pintype "passive"))
    )
    (net (code "40") (name "Net-(R43-Pad2)") (class "Default")
      (node (ref "R43") (pin "2") (pinfunction "2_2") (pintype "passive"))
      (node (ref "R48") (pin "1") (pinfunction "1_1") (pintype "passive"))
      (node (ref "R52") (pin "2") (pinfunction "2_2") (pintype "passive"))
      (node (ref "R57") (pin "1") (pinfunction "1_1") (pintype "passive"))
    )
    (net (code "41") (name "Net-(R44-Pad2)") (class "Default")
      (node (ref "R44") (pin "2") (pinfunction "2_2") (pintype "passive"))
      (node (ref "R48") (pin "2") (pinfunction "2_2") (pintype "passive"))
      (node (ref "R49") (pin "1") (pinfunction "1_1") (pintype "passive"))
      (node (ref "R53") (pin "2") (pinfunction "2_2") (pintype "passive"))
    )
    (net (code "42") (name "Net-(R45-Pad2)") (class "Default")
      (node (ref "R45") (pin "2") (pinfunction "2_2") (pintype "passive"))
      (node (ref "R49") (pin "2") (pinfunction "2_2") (pintype "passive"))
      (node (ref "R50") (pin "1") (pinfunction "1_1") (pintype "passive"))
      (node (ref "R54") (pin "2") (pinfunction "2_2") (pintype "passive"))
    )
    (net (code "43") (name "Net-(R46-Pad2)") (class "Default")
      (node (ref "R46") (pin "2") (pinfunction "2_2") (pintype "passive"))
      (node (ref "R50") (pin "2") (pinfunction "2_2") (pintype "passive"))
      (node (ref "R51") (pin "2") (pinfunction "2_2") (pintype "passive"))
      (node (ref "R55") (pin "2") (pinfunction "2_2") (pintype "passive"))
    )
    (net (code "44") (name "Net-(R47-Pad2)") (class "Default")
      (node (ref "R47") (pin "2") (pinfunction "2_2") (pintype "passive"))
      (node (ref "R51") (pin "1") (pinfunction "1_1") (pintype "passive"))
      (node (ref "R56") (pin "2") (pinfunction "2_2") (pintype "passive"))
      (node (ref "R58") (pin "1") (pinfunction "1_1") (pintype "passive"))
    )
    (net (code "45") (name "Net-(R59-Pad1)") (class "Default")
      (node (ref "R59") (pin "1") (pinfunction "1_1") (pintype "passive"))
      (node (ref "TR1") (pin "3") (pinfunction "P1_3") (pintype "passive"))
    )
    (net (code "46") (name "Net-(TR1-NC)") (class "Default")
      (node (ref "C30") (pin "2") (pinfunction "2_2") (pintype "passive"))
      (node (ref "TR1") (pin "5") (pinfunction "NC_5") (pintype "passive"))
    )
    (net (code "47") (name "VCCP_5V0") (class "Default")
      (node (ref "L6") (pin "2") (pinfunction "2_2") (pintype "passive"))
      (node (ref "L7") (pin "1") (pinfunction "1_1") (pintype "passive"))
    )
    (net (code "48") (name "VCCP_12V0_A") (class "Default")
      (node (ref "C12") (pin "2") (pinfunction "2_2") (pintype "passive"))
      (node (ref "C13") (pin "2") (pinfunction "2_2") (pintype "passive"))
      (node (ref "R5") (pin "1") (pinfunction "1_1") (pintype "passive"))
    )
  )
)
